# B.net
KiCad netlist of a schematic drawn in EAGLE
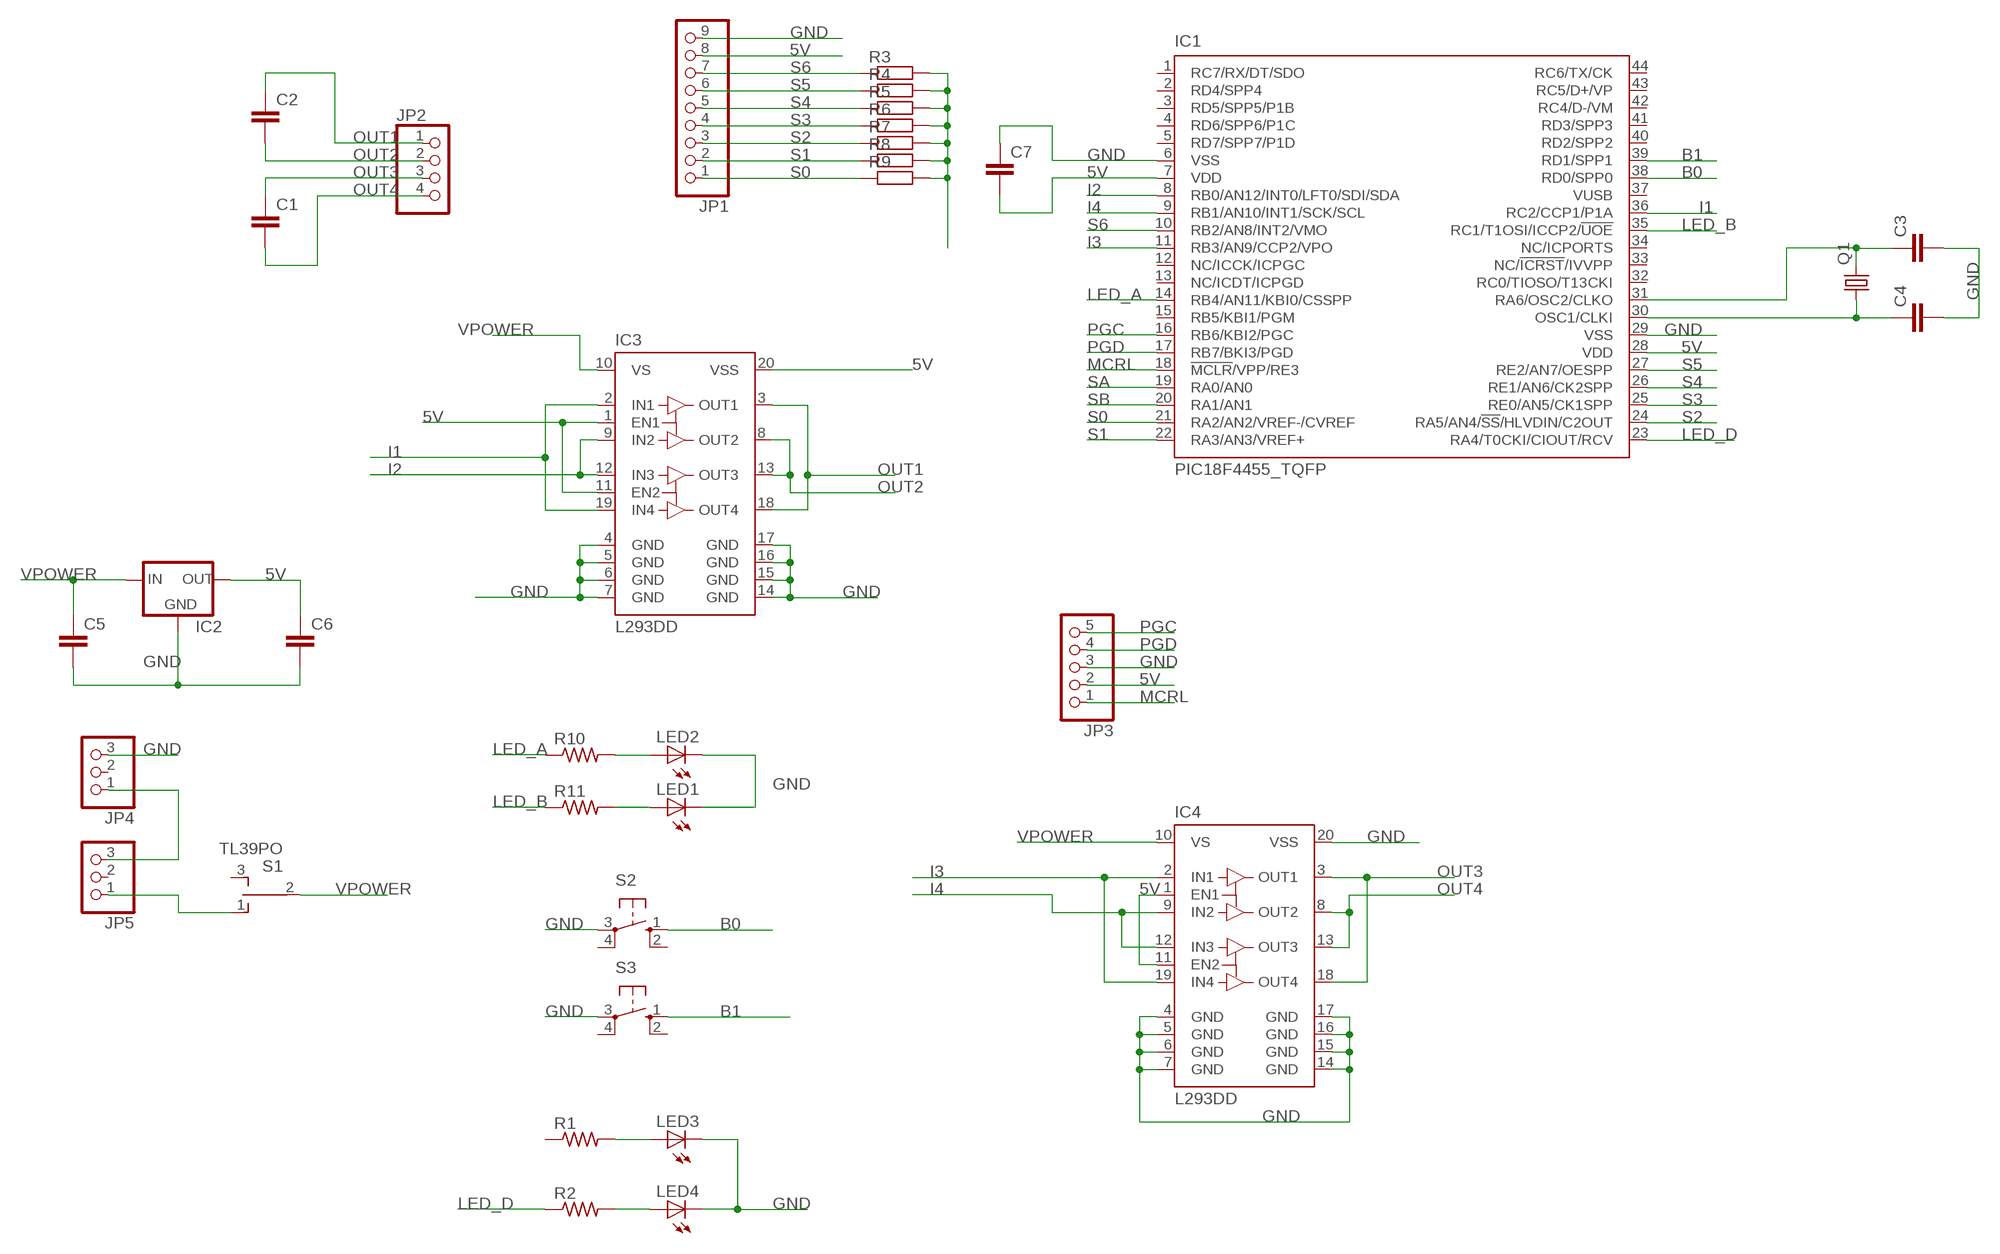
[diagram p0: schematic, sheet 1]

(export (version "E")
  (design (tool "Eeschema 10.0.6"))
  (components
    (comp (ref "C1")
      (value "C2,5-3")
      (footprint "eagle-import:C2.5-3")
      (libsource (lib "eagle-import") (part "C2,5-3"))
    )
    (comp (ref "C2")
      (value "C2,5-3")
      (footprint "eagle-import:C2.5-3")
      (libsource (lib "eagle-import") (part "C2,5-3"))
    )
    (comp (ref "C3")
      (value "C2,5-3")
      (footprint "eagle-import:C2.5-3")
      (libsource (lib "eagle-import") (part "C2,5-3"))
    )
    (comp (ref "C4")
      (value "C2,5-3")
      (footprint "eagle-import:C2.5-3")
      (libsource (lib "eagle-import") (part "C2,5-3"))
    )
    (comp (ref "C5")
      (value "C2,5-3")
      (footprint "eagle-import:C2.5-3")
      (libsource (lib "eagle-import") (part "C2,5-3"))
    )
    (comp (ref "C6")
      (value "C2,5-3")
      (footprint "eagle-import:C2.5-3")
      (libsource (lib "eagle-import") (part "C2,5-3"))
    )
    (comp (ref "C7")
      (value "C2,5-3")
      (footprint "eagle-import:C2.5-3")
      (libsource (lib "eagle-import") (part "C2,5-3"))
    )
    (comp (ref "IC1")
      (value "PIC18F4455_TQFP")
      (footprint "eagle-import:TQFP44")
      (fields (field (name "MF") "MICROCHIP") (field (name "MPN") "PIC18F4455-I/PT"))
      (libsource (lib "eagle-import") (part "PIC18F4_TQFP455"))
    )
    (comp (ref "IC2")
      (value "78XXS")
      (footprint "eagle-import:78XXS")
      (libsource (lib "eagle-import") (part "78XXS"))
    )
    (comp (ref "IC3")
      (value "L293DD")
      (footprint "eagle-import:SO20")
      (libsource (lib "eagle-import") (part "L293DD"))
    )
    (comp (ref "IC4")
      (value "L293DD")
      (footprint "eagle-import:SO20")
      (libsource (lib "eagle-import") (part "L293DD"))
    )
    (comp (ref "JP1")
      (value "PINHD-1X9")
      (footprint "eagle-import:1X09")
      (libsource (lib "eagle-import") (part "PINHD-1X9"))
    )
    (comp (ref "JP2")
      (value "PINHD-1X4")
      (footprint "eagle-import:1X04")
      (libsource (lib "eagle-import") (part "PINHD-1X4"))
    )
    (comp (ref "JP3")
      (value "PINHD-1X5")
      (footprint "eagle-import:1X05")
      (libsource (lib "eagle-import") (part "PINHD-1X5"))
    )
    (comp (ref "JP4")
      (value "PINHD-1X3")
      (footprint "eagle-import:1X03")
      (libsource (lib "eagle-import") (part "PINHD-1X3"))
    )
    (comp (ref "JP5")
      (value "PINHD-1X3")
      (footprint "eagle-import:1X03")
      (libsource (lib "eagle-import") (part "PINHD-1X3"))
    )
    (comp (ref "LED1")
      (value "LEDCHIPLED_1206")
      (footprint "eagle-import:CHIPLED_1206")
      (libsource (lib "eagle-import") (part "LEDCHIPLED_1206"))
    )
    (comp (ref "LED2")
      (value "LEDCHIPLED_1206")
      (footprint "eagle-import:CHIPLED_1206")
      (libsource (lib "eagle-import") (part "LEDCHIPLED_1206"))
    )
    (comp (ref "LED3")
      (value "LEDCHIPLED_1206")
      (footprint "eagle-import:CHIPLED_1206")
      (libsource (lib "eagle-import") (part "LEDCHIPLED_1206"))
    )
    (comp (ref "LED4")
      (value "LEDCHIPLED_1206")
      (footprint "eagle-import:CHIPLED_1206")
      (libsource (lib "eagle-import") (part "LEDCHIPLED_1206"))
    )
    (comp (ref "Q1")
      (value "CRYSTALHC49S")
      (footprint "eagle-import:HC49_S")
      (libsource (lib "eagle-import") (part "CRYSTALHC49S"))
    )
    (comp (ref "R1")
      (value "R-US_R0805")
      (footprint "eagle-import:R0805")
      (libsource (lib "eagle-import") (part "resistor_R-US_R0805"))
    )
    (comp (ref "R2")
      (value "R-US_R0805")
      (footprint "eagle-import:R0805")
      (libsource (lib "eagle-import") (part "resistor_R-US_R0805"))
    )
    (comp (ref "R3")
      (value "R-EU_M0805")
      (footprint "eagle-import:M0805")
      (libsource (lib "eagle-import") (part "R-EU_M0805"))
    )
    (comp (ref "R4")
      (value "R-EU_M0805")
      (footprint "eagle-import:M0805")
      (libsource (lib "eagle-import") (part "R-EU_M0805"))
    )
    (comp (ref "R5")
      (value "R-EU_M0805")
      (footprint "eagle-import:M0805")
      (libsource (lib "eagle-import") (part "R-EU_M0805"))
    )
    (comp (ref "R6")
      (value "R-EU_M0805")
      (footprint "eagle-import:M0805")
      (libsource (lib "eagle-import") (part "R-EU_M0805"))
    )
    (comp (ref "R7")
      (value "R-EU_M0805")
      (footprint "eagle-import:M0805")
      (libsource (lib "eagle-import") (part "R-EU_M0805"))
    )
    (comp (ref "R8")
      (value "R-EU_M0805")
      (footprint "eagle-import:M0805")
      (libsource (lib "eagle-import") (part "R-EU_M0805"))
    )
    (comp (ref "R9")
      (value "R-EU_M0805")
      (footprint "eagle-import:M0805")
      (libsource (lib "eagle-import") (part "R-EU_M0805"))
    )
    (comp (ref "R10")
      (value "R-US_M0805")
      (footprint "eagle-import:M0805")
      (libsource (lib "eagle-import") (part "R-US_M0805"))
    )
    (comp (ref "R11")
      (value "R-US_M0805")
      (footprint "eagle-import:M0805")
      (libsource (lib "eagle-import") (part "R-US_M0805"))
    )
    (comp (ref "S1")
      (value "TL39PO")
      (footprint "eagle-import:TL3XPO")
      (libsource (lib "eagle-import") (part "TL39PO"))
    )
    (comp (ref "S2")
      (value "10-XX")
      (footprint "eagle-import:B3F-10XX")
      (fields (field (name "MPN") "B3F-1000"))
      (libsource (lib "eagle-import") (part "10-XX"))
    )
    (comp (ref "S3")
      (value "10-XX")
      (footprint "eagle-import:B3F-10XX")
      (fields (field (name "MPN") "B3F-1000"))
      (libsource (lib "eagle-import") (part "10-XX"))
    )
  )
  (nets
    (net (code "1") (name "/5V") (class "Default")
      (node (ref "C6") (pin "1") (pinfunction "1_1") (pintype "passive"))
      (node (ref "C7") (pin "2") (pinfunction "2_2") (pintype "passive"))
      (node (ref "IC1") (pin "28") (pinfunction "VDD_28") (pintype "power_in"))
      (node (ref "IC1") (pin "7") (pinfunction "VDD_7") (pintype "power_in"))
      (node (ref "IC2") (pin "OUT") (pinfunction "OUT_OUT") (pintype "passive"))
      (node (ref "IC3") (pin "1") (pinfunction "EN1_1") (pintype "input"))
      (node (ref "IC3") (pin "11") (pinfunction "EN2_11") (pintype "input"))
      (node (ref "IC3") (pin "20") (pinfunction "VSS_20") (pintype "power_in"))
      (node (ref "IC4") (pin "1") (pinfunction "EN1_1") (pintype "input"))
      (node (ref "IC4") (pin "11") (pinfunction "EN2_11") (pintype "input"))
      (node (ref "JP1") (pin "8") (pinfunction "8_8") (pintype "passive"))
      (node (ref "JP3") (pin "2") (pinfunction "2_2") (pintype "passive"))
      (node (ref "R3") (pin "2") (pinfunction "2_2") (pintype "passive"))
      (node (ref "R4") (pin "2") (pinfunction "2_2") (pintype "passive"))
      (node (ref "R5") (pin "2") (pinfunction "2_2") (pintype "passive"))
      (node (ref "R6") (pin "2") (pinfunction "2_2") (pintype "passive"))
      (node (ref "R7") (pin "2") (pinfunction "2_2") (pintype "passive"))
      (node (ref "R8") (pin "2") (pinfunction "2_2") (pintype "passive"))
      (node (ref "R9") (pin "2") (pinfunction "2_2") (pintype "passive"))
    )
    (net (code "2") (name "/B0") (class "Default")
      (node (ref "IC1") (pin "38") (pinfunction "RD0/SPP0_38") (pintype "bidirectional"))
      (node (ref "S2") (pin "1") (pinfunction "S_1") (pintype "passive"))
    )
    (net (code "3") (name "/B1") (class "Default")
      (node (ref "IC1") (pin "39") (pinfunction "RD1/SPP1_39") (pintype "bidirectional"))
      (node (ref "S3") (pin "1") (pinfunction "S_1") (pintype "passive"))
    )
    (net (code "4") (name "/GND") (class "Default")
      (node (ref "C3") (pin "2") (pinfunction "2_2") (pintype "passive"))
      (node (ref "C4") (pin "2") (pinfunction "2_2") (pintype "passive"))
      (node (ref "C5") (pin "2") (pinfunction "2_2") (pintype "passive"))
      (node (ref "C6") (pin "2") (pinfunction "2_2") (pintype "passive"))
      (node (ref "C7") (pin "1") (pinfunction "1_1") (pintype "passive"))
      (node (ref "IC1") (pin "29") (pinfunction "VSS_29") (pintype "power_in"))
      (node (ref "IC1") (pin "6") (pinfunction "VSS_6") (pintype "power_in"))
      (node (ref "IC2") (pin "GND") (pinfunction "GND_GND") (pintype "input"))
      (node (ref "IC3") (pin "14") (pinfunction "GND_14") (pintype "power_in"))
      (node (ref "IC3") (pin "15") (pinfunction "GND_15") (pintype "power_in"))
      (node (ref "IC3") (pin "16") (pinfunction "GND_16") (pintype "power_in"))
      (node (ref "IC3") (pin "17") (pinfunction "GND_17") (pintype "power_in"))
      (node (ref "IC3") (pin "4") (pinfunction "GND_4") (pintype "power_in"))
      (node (ref "IC3") (pin "5") (pinfunction "GND_5") (pintype "power_in"))
      (node (ref "IC3") (pin "6") (pinfunction "GND_6") (pintype "power_in"))
      (node (ref "IC3") (pin "7") (pinfunction "GND_7") (pintype "power_in"))
      (node (ref "IC4") (pin "14") (pinfunction "GND_14") (pintype "power_in"))
      (node (ref "IC4") (pin "15") (pinfunction "GND_15") (pintype "power_in"))
      (node (ref "IC4") (pin "16") (pinfunction "GND_16") (pintype "power_in"))
      (node (ref "IC4") (pin "17") (pinfunction "GND_17") (pintype "power_in"))
      (node (ref "IC4") (pin "20") (pinfunction "VSS_20") (pintype "power_in"))
      (node (ref "IC4") (pin "4") (pinfunction "GND_4") (pintype "power_in"))
      (node (ref "IC4") (pin "5") (pinfunction "GND_5") (pintype "power_in"))
      (node (ref "IC4") (pin "6") (pinfunction "GND_6") (pintype "power_in"))
      (node (ref "IC4") (pin "7") (pinfunction "GND_7") (pintype "power_in"))
      (node (ref "JP1") (pin "9") (pinfunction "9_9") (pintype "passive"))
      (node (ref "JP3") (pin "3") (pinfunction "3_3") (pintype "passive"))
      (node (ref "JP4") (pin "3") (pinfunction "3_3") (pintype "passive"))
      (node (ref "LED1") (pin "C") (pinfunction "C_C") (pintype "passive"))
      (node (ref "LED2") (pin "C") (pinfunction "C_C") (pintype "passive"))
      (node (ref "LED3") (pin "C") (pinfunction "C_C") (pintype "passive"))
      (node (ref "LED4") (pin "C") (pinfunction "C_C") (pintype "passive"))
      (node (ref "S2") (pin "3") (pinfunction "P_3") (pintype "passive"))
      (node (ref "S3") (pin "3") (pinfunction "P_3") (pintype "passive"))
    )
    (net (code "5") (name "/I1") (class "Default")
      (node (ref "IC1") (pin "36") (pinfunction "RC2/CCP1/P1A_36") (pintype "bidirectional"))
      (node (ref "IC3") (pin "19") (pinfunction "IN4_19") (pintype "input"))
      (node (ref "IC3") (pin "2") (pinfunction "IN1_2") (pintype "input"))
    )
    (net (code "6") (name "/I2") (class "Default")
      (node (ref "IC1") (pin "8") (pinfunction "RB0/AN12/INT0/LFT0/SDI/SDA_8") (pintype "bidirectional"))
      (node (ref "IC3") (pin "12") (pinfunction "IN3_12") (pintype "input"))
      (node (ref "IC3") (pin "9") (pinfunction "IN2_9") (pintype "input"))
    )
    (net (code "7") (name "/I3") (class "Default")
      (node (ref "IC1") (pin "11") (pinfunction "RB3/AN9/CCP2/VPO_11") (pintype "bidirectional"))
      (node (ref "IC4") (pin "19") (pinfunction "IN4_19") (pintype "input"))
      (node (ref "IC4") (pin "2") (pinfunction "IN1_2") (pintype "input"))
    )
    (net (code "8") (name "/I4") (class "Default")
      (node (ref "IC1") (pin "9") (pinfunction "RB1/AN10/INT1/SCK/SCL_9") (pintype "bidirectional"))
      (node (ref "IC4") (pin "12") (pinfunction "IN3_12") (pintype "input"))
      (node (ref "IC4") (pin "9") (pinfunction "IN2_9") (pintype "input"))
    )
    (net (code "9") (name "/LED_A") (class "Default")
      (node (ref "IC1") (pin "14") (pinfunction "RB4/AN11/KBI0/CSSPP_14") (pintype "bidirectional"))
      (node (ref "R10") (pin "1") (pinfunction "1_1") (pintype "passive"))
    )
    (net (code "10") (name "/LED_B") (class "Default")
      (node (ref "IC1") (pin "35") (pinfunction "RC1/T1OSI/ICCP2/~{UOE}_35") (pintype "bidirectional"))
      (node (ref "R11") (pin "1") (pinfunction "1_1") (pintype "passive"))
    )
    (net (code "11") (name "/LED_D") (class "Default")
      (node (ref "IC1") (pin "23") (pinfunction "RA4/T0CKI/CIOUT/RCV_23") (pintype "bidirectional"))
      (node (ref "R2") (pin "1") (pinfunction "1_1") (pintype "passive"))
    )
    (net (code "12") (name "/MCRL") (class "Default")
      (node (ref "IC1") (pin "18") (pinfunction "~{MCLR}/VPP/RE3_18") (pintype "input"))
      (node (ref "JP3") (pin "1") (pinfunction "1_1") (pintype "passive"))
    )
    (net (code "13") (name "/OUT1") (class "Default")
      (node (ref "C2") (pin "1") (pinfunction "1_1") (pintype "passive"))
      (node (ref "IC3") (pin "18") (pinfunction "OUT4_18") (pintype "output"))
      (node (ref "IC3") (pin "3") (pinfunction "OUT1_3") (pintype "output"))
      (node (ref "JP2") (pin "1") (pinfunction "1_1") (pintype "passive"))
    )
    (net (code "14") (name "/OUT2") (class "Default")
      (node (ref "C2") (pin "2") (pinfunction "2_2") (pintype "passive"))
      (node (ref "IC3") (pin "13") (pinfunction "OUT3_13") (pintype "output"))
      (node (ref "IC3") (pin "8") (pinfunction "OUT2_8") (pintype "output"))
      (node (ref "JP2") (pin "2") (pinfunction "2_2") (pintype "passive"))
    )
    (net (code "15") (name "/OUT3") (class "Default")
      (node (ref "C1") (pin "1") (pinfunction "1_1") (pintype "passive"))
      (node (ref "IC4") (pin "18") (pinfunction "OUT4_18") (pintype "output"))
      (node (ref "IC4") (pin "3") (pinfunction "OUT1_3") (pintype "output"))
      (node (ref "JP2") (pin "3") (pinfunction "3_3") (pintype "passive"))
    )
    (net (code "16") (name "/OUT4") (class "Default")
      (node (ref "C1") (pin "2") (pinfunction "2_2") (pintype "passive"))
      (node (ref "IC4") (pin "13") (pinfunction "OUT3_13") (pintype "output"))
      (node (ref "IC4") (pin "8") (pinfunction "OUT2_8") (pintype "output"))
      (node (ref "JP2") (pin "4") (pinfunction "4_4") (pintype "passive"))
    )
    (net (code "17") (name "/PGC") (class "Default")
      (node (ref "IC1") (pin "16") (pinfunction "RB6/KBI2/PGC_16") (pintype "bidirectional"))
      (node (ref "JP3") (pin "5") (pinfunction "5_5") (pintype "passive"))
    )
    (net (code "18") (name "/PGD") (class "Default")
      (node (ref "IC1") (pin "17") (pinfunction "RB7/BKI3/PGD_17") (pintype "bidirectional"))
      (node (ref "JP3") (pin "4") (pinfunction "4_4") (pintype "passive"))
    )
    (net (code "19") (name "/S0") (class "Default")
      (node (ref "IC1") (pin "21") (pinfunction "RA2/AN2/VREF-/CVREF_21") (pintype "bidirectional"))
      (node (ref "JP1") (pin "1") (pinfunction "1_1") (pintype "passive"))
      (node (ref "R9") (pin "1") (pinfunction "1_1") (pintype "passive"))
    )
    (net (code "20") (name "/S1") (class "Default")
      (node (ref "IC1") (pin "22") (pinfunction "RA3/AN3/VREF+_22") (pintype "bidirectional"))
      (node (ref "JP1") (pin "2") (pinfunction "2_2") (pintype "passive"))
      (node (ref "R8") (pin "1") (pinfunction "1_1") (pintype "passive"))
    )
    (net (code "21") (name "/S2") (class "Default")
      (node (ref "IC1") (pin "24") (pinfunction "RA5/AN4/~{SS}/HLVDIN/C2OUT_24") (pintype "bidirectional"))
      (node (ref "JP1") (pin "3") (pinfunction "3_3") (pintype "passive"))
      (node (ref "R7") (pin "1") (pinfunction "1_1") (pintype "passive"))
    )
    (net (code "22") (name "/S3") (class "Default")
      (node (ref "IC1") (pin "25") (pinfunction "RE0/AN5/CK1SPP_25") (pintype "bidirectional"))
      (node (ref "JP1") (pin "4") (pinfunction "4_4") (pintype "passive"))
      (node (ref "R6") (pin "1") (pinfunction "1_1") (pintype "passive"))
    )
    (net (code "23") (name "/S4") (class "Default")
      (node (ref "IC1") (pin "26") (pinfunction "RE1/AN6/CK2SPP_26") (pintype "bidirectional"))
      (node (ref "JP1") (pin "5") (pinfunction "5_5") (pintype "passive"))
      (node (ref "R5") (pin "1") (pinfunction "1_1") (pintype "passive"))
    )
    (net (code "24") (name "/S5") (class "Default")
      (node (ref "IC1") (pin "27") (pinfunction "RE2/AN7/OESPP_27") (pintype "bidirectional"))
      (node (ref "JP1") (pin "6") (pinfunction "6_6") (pintype "passive"))
      (node (ref "R4") (pin "1") (pinfunction "1_1") (pintype "passive"))
    )
    (net (code "25") (name "/S6") (class "Default")
      (node (ref "IC1") (pin "10") (pinfunction "RB2/AN8/INT2/VMO_10") (pintype "bidirectional"))
      (node (ref "JP1") (pin "7") (pinfunction "7_7") (pintype "passive"))
      (node (ref "R3") (pin "1") (pinfunction "1_1") (pintype "passive"))
    )
    (net (code "26") (name "/SA") (class "Default")
      (node (ref "IC1") (pin "19") (pinfunction "RA0/AN0_19") (pintype "bidirectional"))
    )
    (net (code "27") (name "/SB") (class "Default")
      (node (ref "IC1") (pin "20") (pinfunction "RA1/AN1_20") (pintype "bidirectional"))
    )
    (net (code "28") (name "/VPOWER") (class "Default")
      (node (ref "C5") (pin "1") (pinfunction "1_1") (pintype "passive"))
      (node (ref "IC2") (pin "IN") (pinfunction "IN_IN") (pintype "input"))
      (node (ref "IC3") (pin "10") (pinfunction "VS_10") (pintype "power_in"))
      (node (ref "IC4") (pin "10") (pinfunction "VS_10") (pintype "power_in"))
      (node (ref "S1") (pin "2") (pinfunction "P_2") (pintype "passive"))
    )
    (net (code "29") (name "Net-(IC1-OSC1{slash}CLKI)") (class "Default")
      (node (ref "C4") (pin "1") (pinfunction "1_1") (pintype "passive"))
      (node (ref "IC1") (pin "30") (pinfunction "OSC1/CLKI_30") (pintype "input"))
      (node (ref "Q1") (pin "1") (pinfunction "1_1") (pintype "passive"))
    )
    (net (code "30") (name "Net-(IC1-RA6{slash}OSC2{slash}CLKO)") (class "Default")
      (node (ref "C3") (pin "1") (pinfunction "1_1") (pintype "passive"))
      (node (ref "IC1") (pin "31") (pinfunction "RA6/OSC2/CLKO_31") (pintype "output"))
      (node (ref "Q1") (pin "2") (pinfunction "2_2") (pintype "passive"))
    )
    (net (code "31") (name "Net-(JP4-Pad1)") (class "Default")
      (node (ref "JP4") (pin "1") (pinfunction "1_1") (pintype "passive"))
      (node (ref "JP5") (pin "3") (pinfunction "3_3") (pintype "passive"))
    )
    (net (code "32") (name "Net-(LED1-PadA)") (class "Default")
      (node (ref "LED1") (pin "A") (pinfunction "A_A") (pintype "passive"))
      (node (ref "R11") (pin "2") (pinfunction "2_2") (pintype "passive"))
    )
    (net (code "33") (name "Net-(LED2-PadA)") (class "Default")
      (node (ref "LED2") (pin "A") (pinfunction "A_A") (pintype "passive"))
      (node (ref "R10") (pin "2") (pinfunction "2_2") (pintype "passive"))
    )
    (net (code "34") (name "Net-(LED3-PadA)") (class "Default")
      (node (ref "LED3") (pin "A") (pinfunction "A_A") (pintype "passive"))
      (node (ref "R1") (pin "2") (pinfunction "2_2") (pintype "passive"))
    )
    (net (code "35") (name "Net-(LED4-PadA)") (class "Default")
      (node (ref "LED4") (pin "A") (pinfunction "A_A") (pintype "passive"))
      (node (ref "R2") (pin "2") (pinfunction "2_2") (pintype "passive"))
    )
    (net (code "36") (name "Net-(S1-O)") (class "Default")
      (node (ref "JP5") (pin "1") (pinfunction "1_1") (pintype "passive"))
      (node (ref "S1") (pin "1") (pinfunction "O_1") (pintype "passive"))
    )
    (net (code "37") (name "unconnected-(IC1-NC{slash}ICCK{slash}ICPGC-Pad12)") (class "Default")
      (node (ref "IC1") (pin "12") (pinfunction "NC/ICCK/ICPGC_12") (pintype "bidirectional"))
    )
    (net (code "38") (name "unconnected-(IC1-NC{slash}ICDT{slash}ICPGD-Pad13)") (class "Default")
      (node (ref "IC1") (pin "13") (pinfunction "NC/ICDT/ICPGD_13") (pintype "bidirectional"))
    )
    (net (code "39") (name "unconnected-(IC1-NC{slash}ICPORTS-Pad34)") (class "Default")
      (node (ref "IC1") (pin "34") (pinfunction "NC/ICPORTS_34") (pintype "input"))
    )
    (net (code "40") (name "unconnected-(IC1-NC{slash}~{ICRST}{slash}IVVPP-Pad33)") (class "Default")
      (node (ref "IC1") (pin "33") (pinfunction "NC/~{ICRST}/IVVPP_33") (pintype "input"))
    )
    (net (code "41") (name "unconnected-(IC1-RB5{slash}KBI1{slash}PGM-Pad15)") (class "Default")
      (node (ref "IC1") (pin "15") (pinfunction "RB5/KBI1/PGM_15") (pintype "bidirectional"))
    )
    (net (code "42") (name "unconnected-(IC1-RC0{slash}TIOSO{slash}T13CKI-Pad32)") (class "Default")
      (node (ref "IC1") (pin "32") (pinfunction "RC0/TIOSO/T13CKI_32") (pintype "bidirectional"))
    )
    (net (code "43") (name "unconnected-(IC1-RC4{slash}D-{slash}VM-Pad42)") (class "Default")
      (node (ref "IC1") (pin "42") (pinfunction "RC4/D-/VM_42") (pintype "bidirectional"))
    )
    (net (code "44") (name "unconnected-(IC1-RC5{slash}D+{slash}VP-Pad43)") (class "Default")
      (node (ref "IC1") (pin "43") (pinfunction "RC5/D+/VP_43") (pintype "bidirectional"))
    )
    (net (code "45") (name "unconnected-(IC1-RC6{slash}TX{slash}CK-Pad44)") (class "Default")
      (node (ref "IC1") (pin "44") (pinfunction "RC6/TX/CK_44") (pintype "bidirectional"))
    )
    (net (code "46") (name "unconnected-(IC1-RC7{slash}RX{slash}DT{slash}SDO-Pad1)") (class "Default")
      (node (ref "IC1") (pin "1") (pinfunction "RC7/RX/DT/SDO_1") (pintype "bidirectional"))
    )
    (net (code "47") (name "unconnected-(IC1-RD2{slash}SPP2-Pad40)") (class "Default")
      (node (ref "IC1") (pin "40") (pinfunction "RD2/SPP2_40") (pintype "bidirectional"))
    )
    (net (code "48") (name "unconnected-(IC1-RD3{slash}SPP3-Pad41)") (class "Default")
      (node (ref "IC1") (pin "41") (pinfunction "RD3/SPP3_41") (pintype "bidirectional"))
    )
    (net (code "49") (name "unconnected-(IC1-RD4{slash}SPP4-Pad2)") (class "Default")
      (node (ref "IC1") (pin "2") (pinfunction "RD4/SPP4_2") (pintype "bidirectional"))
    )
    (net (code "50") (name "unconnected-(IC1-RD5{slash}SPP5{slash}P1B-Pad3)") (class "Default")
      (node (ref "IC1") (pin "3") (pinfunction "RD5/SPP5/P1B_3") (pintype "bidirectional"))
    )
    (net (code "51") (name "unconnected-(IC1-RD6{slash}SPP6{slash}P1C-Pad4)") (class "Default")
      (node (ref "IC1") (pin "4") (pinfunction "RD6/SPP6/P1C_4") (pintype "bidirectional"))
    )
    (net (code "52") (name "unconnected-(IC1-RD7{slash}SPP7{slash}P1D-Pad5)") (class "Default")
      (node (ref "IC1") (pin "5") (pinfunction "RD7/SPP7/P1D_5") (pintype "bidirectional"))
    )
    (net (code "53") (name "unconnected-(IC1-VUSB-Pad37)") (class "Default")
      (node (ref "IC1") (pin "37") (pinfunction "VUSB_37") (pintype "bidirectional"))
    )
    (net (code "54") (name "unconnected-(JP4-Pad2)") (class "Default")
      (node (ref "JP4") (pin "2") (pinfunction "2_2") (pintype "passive"))
    )
    (net (code "55") (name "unconnected-(JP5-Pad2)") (class "Default")
      (node (ref "JP5") (pin "2") (pinfunction "2_2") (pintype "passive"))
    )
    (net (code "56") (name "unconnected-(R1-Pad1)") (class "Default")
      (node (ref "R1") (pin "1") (pinfunction "1_1") (pintype "passive"))
    )
    (net (code "57") (name "unconnected-(S1-S-Pad3)") (class "Default")
      (node (ref "S1") (pin "3") (pinfunction "S_3") (pintype "passive"))
    )
    (net (code "58") (name "unconnected-(S2-P1-Pad4)") (class "Default")
      (node (ref "S2") (pin "4") (pinfunction "P1_4") (pintype "passive"))
    )
    (net (code "59") (name "unconnected-(S2-S1-Pad2)") (class "Default")
      (node (ref "S2") (pin "2") (pinfunction "S1_2") (pintype "passive"))
    )
    (net (code "60") (name "unconnected-(S3-P1-Pad4)") (class "Default")
      (node (ref "S3") (pin "4") (pinfunction "P1_4") (pintype "passive"))
    )
    (net (code "61") (name "unconnected-(S3-S1-Pad2)") (class "Default")
      (node (ref "S3") (pin "2") (pinfunction "S1_2") (pintype "passive"))
    )
  )
)
